# P03-UARTs_KEY.net
KiCad netlist of a schematic drawn in Altium Designer
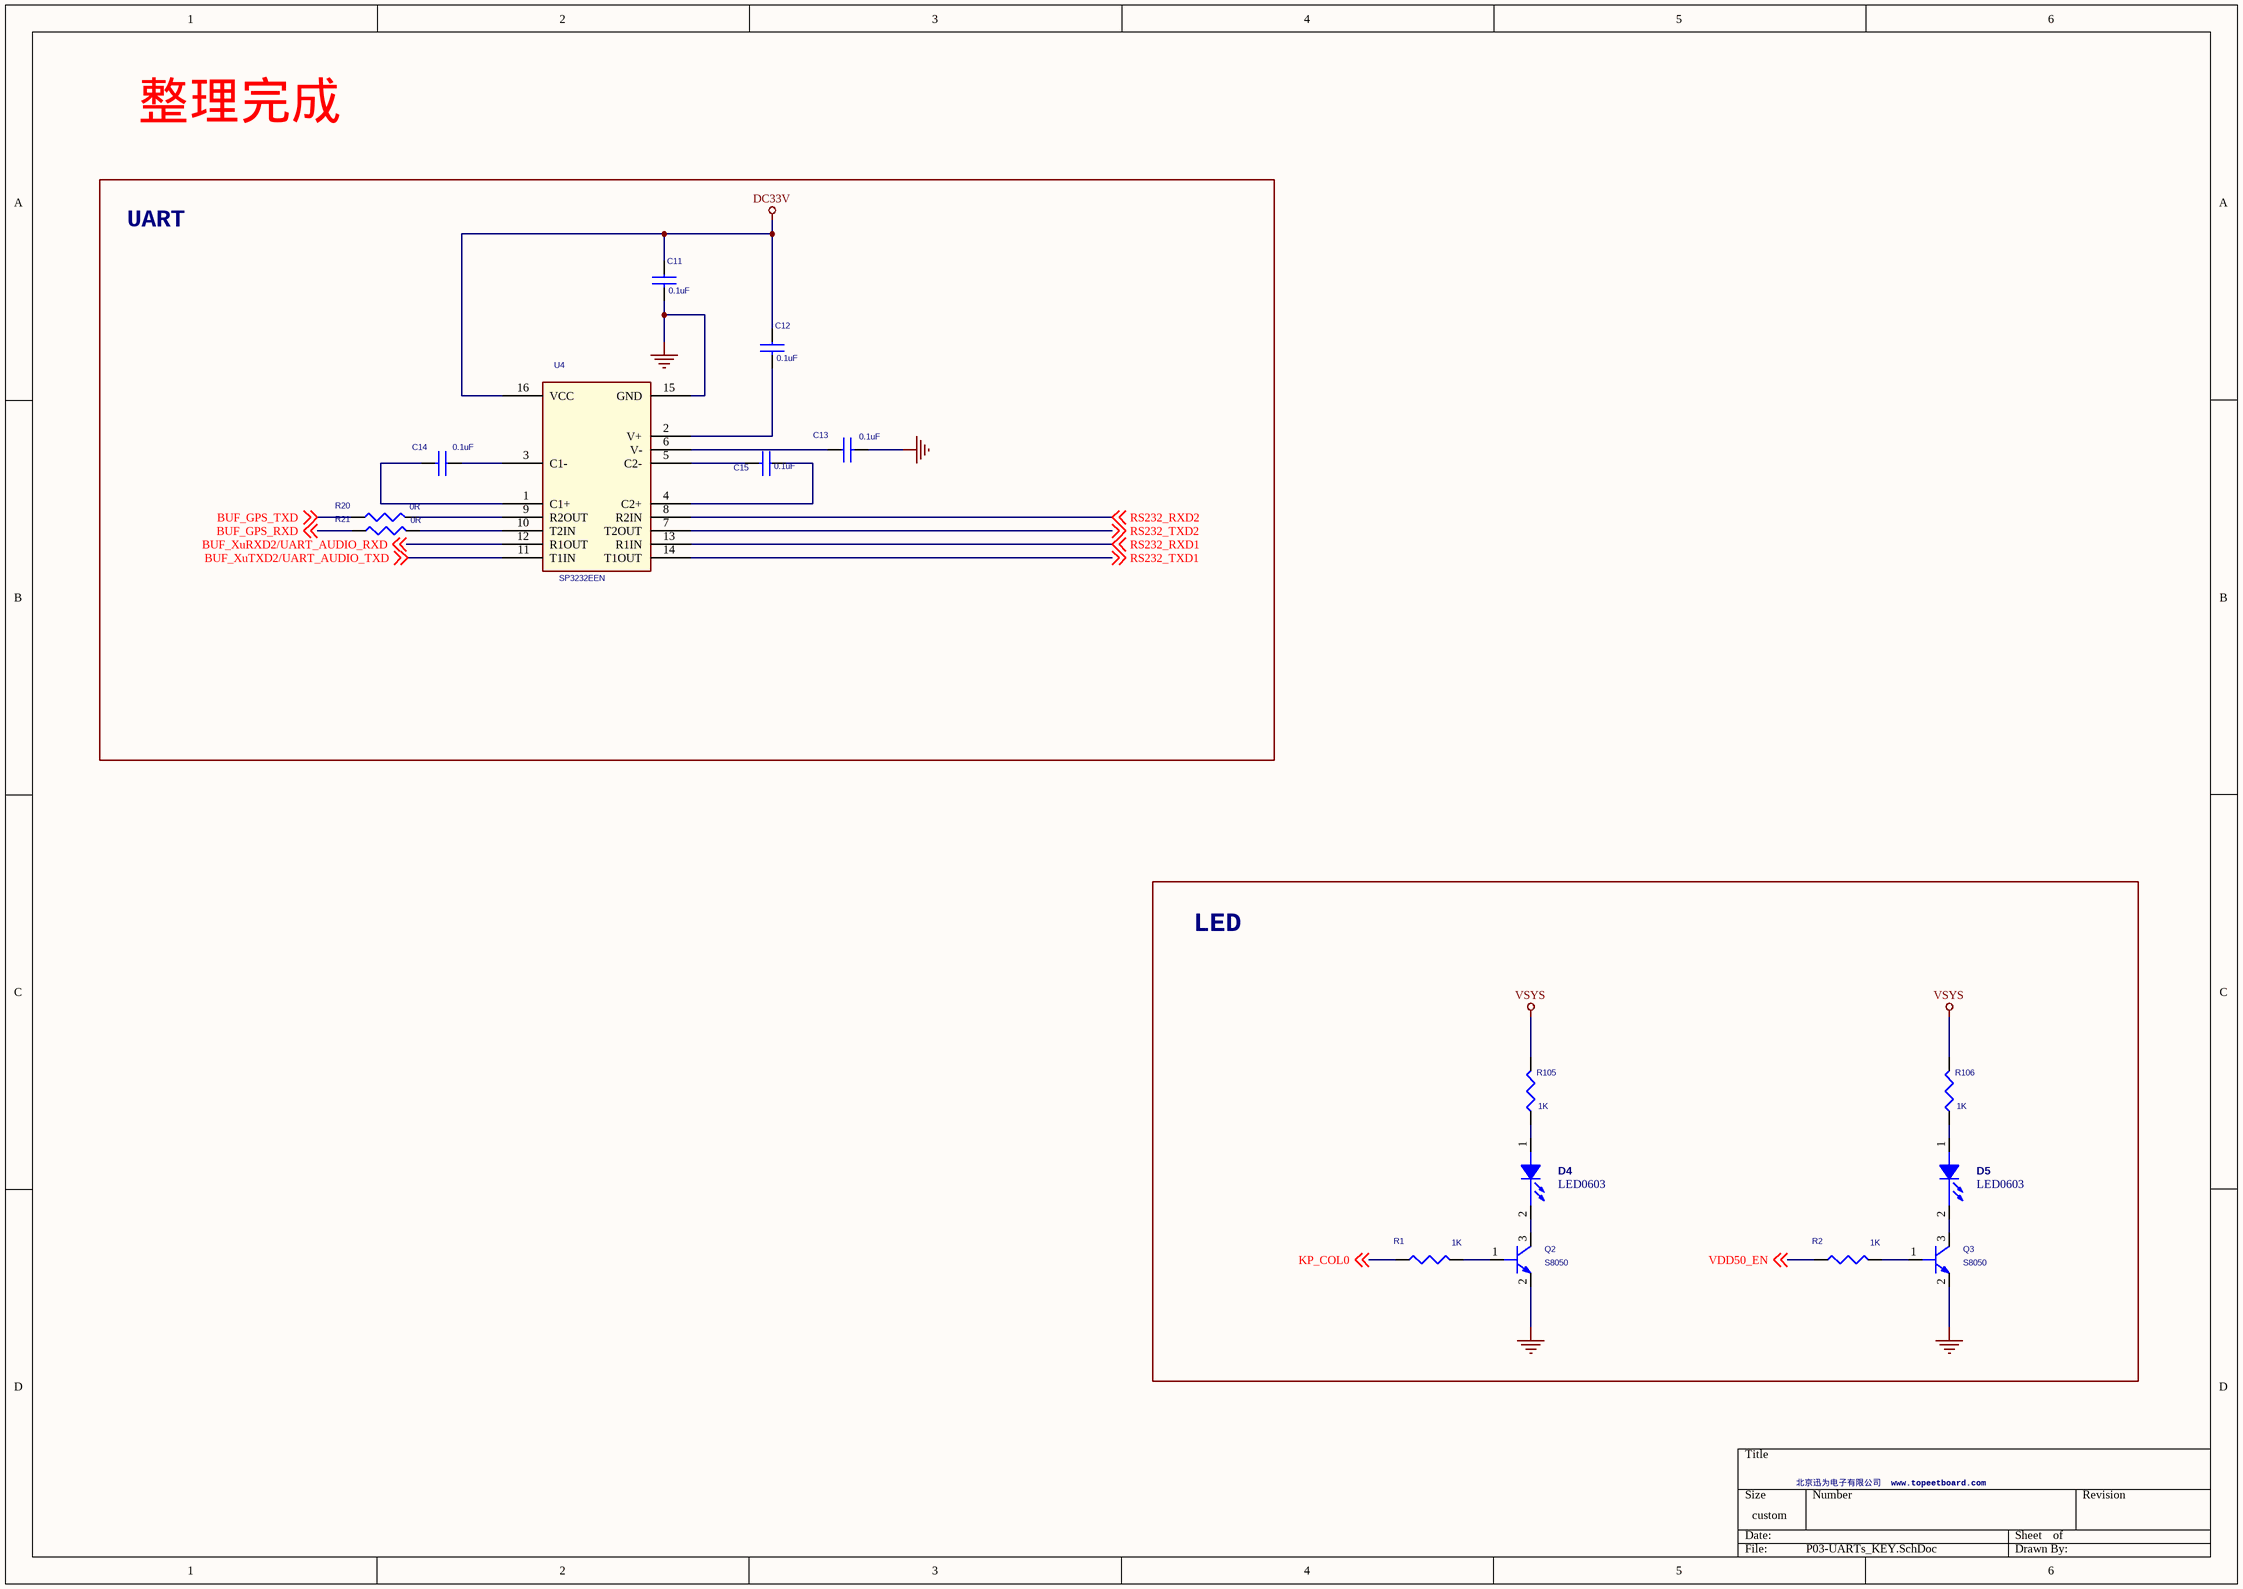
[diagram p0: P03-UARTs_KEY.SchDoc]

(export (version "E")
  (design (tool "Eeschema 10.0.6"))
  (components
    (comp (ref "C11") (value "0.1uF") (footprint "C0603-S") (libsource (lib "*") (part "C0603_0")))
    (comp (ref "C12") (value "0.1uF") (footprint "C0603-S") (libsource (lib "*") (part "C0603_0")))
    (comp (ref "C13") (value "0.1uF") (footprint "C0603-S") (libsource (lib "*") (part "C0603_0")))
    (comp (ref "C14") (value "0.1uF") (footprint "C0603-S") (libsource (lib "*") (part "C0603_0")))
    (comp (ref "C15") (value "0.1uF") (footprint "C0603-S") (libsource (lib "*") (part "C0603_0")))
    (comp (ref "D4") (value "LED0603") (footprint "LED0603") (libsource (lib "*") (part "LED-RED_SMD_1")))
    (comp (ref "D5") (value "LED0603") (footprint "LED0603") (libsource (lib "*") (part "LED-RED_SMD_1")))
    (comp (ref "Q2") (value "S8050") (libsource (lib "*") (part "L14P2/TO_1")))
    (comp (ref "Q3") (value "S8050") (libsource (lib "*") (part "L14P2/TO_1")))
    (comp (ref "R1") (value "1K") (footprint "R0603-S") (libsource (lib "*") (part "R1005_0_Dup1")))
    (comp (ref "R2") (value "1K") (footprint "R0603-S") (libsource (lib "*") (part "R1005_0_Dup1")))
    (comp (ref "R20") (value "0R") (footprint "R0603-S") (libsource (lib "*") (part "R1005_0")))
    (comp (ref "R21") (value "0R") (footprint "R0603-S") (libsource (lib "*") (part "R1005_0")))
    (comp (ref "R105") (value "1K") (footprint "R0603-S") (libsource (lib "*") (part "R1005_0_Dup1")))
    (comp (ref "R106") (value "1K") (footprint "R0603-S") (libsource (lib "*") (part "R1005_0_Dup1")))
    (comp (ref "U4") (value "SP3232EEN") (footprint "SO-16") (libsource (lib "*") (part "MAX3232EEAE")))
  )
  (nets
    (net (code "1") (name "BUF_GPS_RXD") (class "Default")
      (node (ref "R21") (pin "1") (pinfunction "1_1") (pintype "passive"))
    )
    (net (code "2") (name "BUF_GPS_TXD") (class "Default")
      (node (ref "R20") (pin "1") (pinfunction "1_1") (pintype "passive"))
    )
    (net (code "3") (name "BUF_XuRXD2{slash}UART_AUDIO_RXD") (class "Default")
      (node (ref "U4") (pin "12") (pinfunction "R1OUT_12") (pintype "passive"))
    )
    (net (code "4") (name "BUF_XuTXD2{slash}UART_AUDIO_TXD") (class "Default")
      (node (ref "U4") (pin "11") (pinfunction "T1IN_11") (pintype "passive"))
    )
    (net (code "5") (name "DC33V") (class "Default")
      (node (ref "C11") (pin "1") (pinfunction "1_1") (pintype "passive"))
      (node (ref "C12") (pin "1") (pinfunction "1_1") (pintype "passive"))
      (node (ref "U4") (pin "16") (pinfunction "VCC_16") (pintype "power_in"))
    )
    (net (code "6") (name "GND") (class "Default")
      (node (ref "C11") (pin "2") (pinfunction "2_2") (pintype "passive"))
      (node (ref "C13") (pin "2") (pinfunction "2_2") (pintype "passive"))
      (node (ref "Q2") (pin "2") (pinfunction "EMITTER_2") (pintype "passive"))
      (node (ref "Q3") (pin "2") (pinfunction "EMITTER_2") (pintype "passive"))
      (node (ref "U4") (pin "15") (pinfunction "GND_15") (pintype "power_in"))
    )
    (net (code "7") (name "KP_COL0") (class "Default")
      (node (ref "R1") (pin "2") (pinfunction "2_2") (pintype "passive"))
    )
    (net (code "8") (name "Net-(D4-ANODE)") (class "Default")
      (node (ref "D4") (pin "1") (pinfunction "ANODE_1") (pintype "passive"))
      (node (ref "R105") (pin "1") (pinfunction "1_1") (pintype "passive"))
    )
    (net (code "9") (name "Net-(D4-CATHODE)") (class "Default")
      (node (ref "D4") (pin "2") (pinfunction "CATHODE_2") (pintype "passive"))
      (node (ref "Q2") (pin "3") (pinfunction "COLLECTOR_3") (pintype "passive"))
    )
    (net (code "10") (name "Net-(D5-ANODE)") (class "Default")
      (node (ref "D5") (pin "1") (pinfunction "ANODE_1") (pintype "passive"))
      (node (ref "R106") (pin "1") (pinfunction "1_1") (pintype "passive"))
    )
    (net (code "11") (name "Net-(D5-CATHODE)") (class "Default")
      (node (ref "D5") (pin "2") (pinfunction "CATHODE_2") (pintype "passive"))
      (node (ref "Q3") (pin "3") (pinfunction "COLLECTOR_3") (pintype "passive"))
    )
    (net (code "12") (name "Net-(Q2-BASE)") (class "Default")
      (node (ref "Q2") (pin "1") (pinfunction "BASE_1") (pintype "passive"))
      (node (ref "R1") (pin "1") (pinfunction "1_1") (pintype "passive"))
    )
    (net (code "13") (name "Net-(Q3-BASE)") (class "Default")
      (node (ref "Q3") (pin "1") (pinfunction "BASE_1") (pintype "passive"))
      (node (ref "R2") (pin "1") (pinfunction "1_1") (pintype "passive"))
    )
    (net (code "14") (name "Net-(U4-C1+)") (class "Default")
      (node (ref "C14") (pin "2") (pinfunction "2_2") (pintype "passive"))
      (node (ref "U4") (pin "1") (pinfunction "C1+_1") (pintype "passive"))
    )
    (net (code "15") (name "Net-(U4-C1-)") (class "Default")
      (node (ref "C14") (pin "1") (pinfunction "1_1") (pintype "passive"))
      (node (ref "U4") (pin "3") (pinfunction "C1-_3") (pintype "passive"))
    )
    (net (code "16") (name "Net-(U4-C2+)") (class "Default")
      (node (ref "C15") (pin "1") (pinfunction "1_1") (pintype "passive"))
      (node (ref "U4") (pin "4") (pinfunction "C2+_4") (pintype "passive"))
    )
    (net (code "17") (name "Net-(U4-C2-)") (class "Default")
      (node (ref "C15") (pin "2") (pinfunction "2_2") (pintype "passive"))
      (node (ref "U4") (pin "5") (pinfunction "C2-_5") (pintype "passive"))
    )
    (net (code "18") (name "Net-(U4-R2OUT)") (class "Default")
      (node (ref "R20") (pin "2") (pinfunction "2_2") (pintype "passive"))
      (node (ref "U4") (pin "9") (pinfunction "R2OUT_9") (pintype "passive"))
    )
    (net (code "19") (name "Net-(U4-T2IN)") (class "Default")
      (node (ref "R21") (pin "2") (pinfunction "2_2") (pintype "passive"))
      (node (ref "U4") (pin "10") (pinfunction "T2IN_10") (pintype "passive"))
    )
    (net (code "20") (name "Net-(U4-V+)") (class "Default")
      (node (ref "C12") (pin "2") (pinfunction "2_2") (pintype "passive"))
      (node (ref "U4") (pin "2") (pinfunction "V+_2") (pintype "passive"))
    )
    (net (code "21") (name "Net-(U4-V-)") (class "Default")
      (node (ref "C13") (pin "1") (pinfunction "1_1") (pintype "passive"))
      (node (ref "U4") (pin "6") (pinfunction "V-_6") (pintype "passive"))
    )
    (net (code "22") (name "RS232_RXD1") (class "Default")
      (node (ref "U4") (pin "13") (pinfunction "R1IN_13") (pintype "passive"))
    )
    (net (code "23") (name "RS232_RXD2") (class "Default")
      (node (ref "U4") (pin "8") (pinfunction "R2IN_8") (pintype "passive"))
    )
    (net (code "24") (name "RS232_TXD1") (class "Default")
      (node (ref "U4") (pin "14") (pinfunction "T1OUT_14") (pintype "passive"))
    )
    (net (code "25") (name "RS232_TXD2") (class "Default")
      (node (ref "U4") (pin "7") (pinfunction "T2OUT_7") (pintype "passive"))
    )
    (net (code "26") (name "VDD50_EN") (class "Default")
      (node (ref "R2") (pin "2") (pinfunction "2_2") (pintype "passive"))
    )
    (net (code "27") (name "VSYS") (class "Default")
      (node (ref "R105") (pin "2") (pinfunction "2_2") (pintype "passive"))
      (node (ref "R106") (pin "2") (pinfunction "2_2") (pintype "passive"))
    )
  )
)
